# M707X.net
KiCad netlist of a schematic drawn in EAGLE
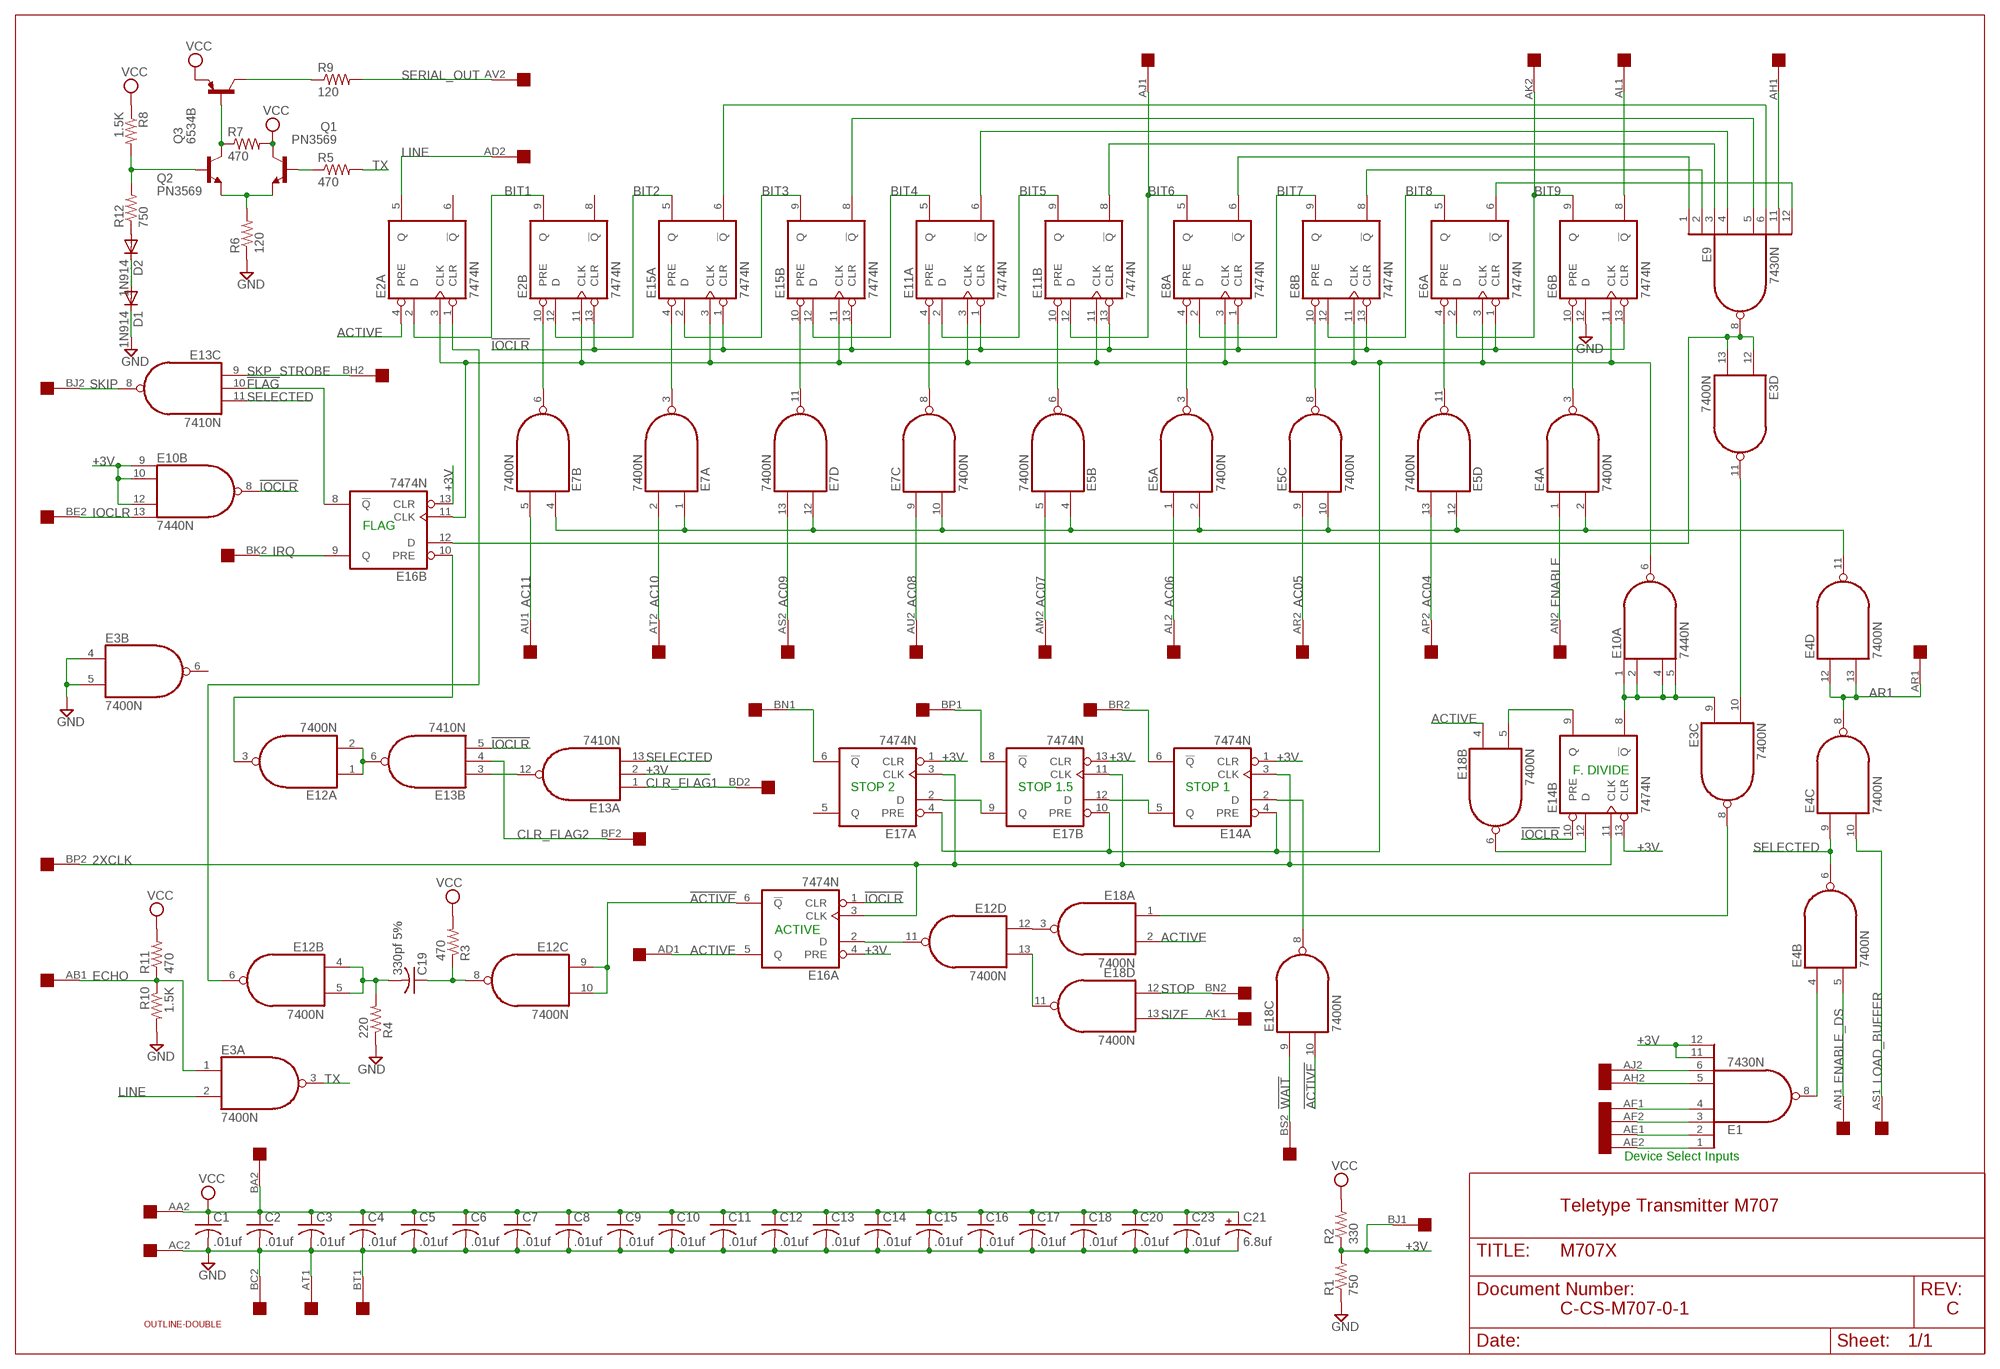
[diagram p0: schematic, sheet 1]

(export (version "E")
  (design (tool "Eeschema 10.0.6"))
  (components
    (comp (ref "C1")
      (value ".01uf")
      (footprint "eagle-import:C050-025X075")
      (libsource (lib "eagle-import") (part "C-US050-025X075"))
    )
    (comp (ref "C2")
      (value ".01uf")
      (footprint "eagle-import:C050-025X075")
      (libsource (lib "eagle-import") (part "C-US050-025X075"))
    )
    (comp (ref "C3")
      (value ".01uf")
      (footprint "eagle-import:C050-025X075")
      (libsource (lib "eagle-import") (part "C-US050-025X075"))
    )
    (comp (ref "C4")
      (value ".01uf")
      (footprint "eagle-import:C050-025X075")
      (libsource (lib "eagle-import") (part "C-US050-025X075"))
    )
    (comp (ref "C5")
      (value ".01uf")
      (footprint "eagle-import:C050-025X075")
      (libsource (lib "eagle-import") (part "C-US050-025X075"))
    )
    (comp (ref "C6")
      (value ".01uf")
      (footprint "eagle-import:C050-025X075")
      (libsource (lib "eagle-import") (part "C-US050-025X075"))
    )
    (comp (ref "C7")
      (value ".01uf")
      (footprint "eagle-import:C050-025X075")
      (libsource (lib "eagle-import") (part "C-US050-025X075"))
    )
    (comp (ref "C8")
      (value ".01uf")
      (footprint "eagle-import:C050-025X075")
      (libsource (lib "eagle-import") (part "C-US050-025X075"))
    )
    (comp (ref "C9")
      (value ".01uf")
      (footprint "eagle-import:C050-025X075")
      (libsource (lib "eagle-import") (part "C-US050-025X075"))
    )
    (comp (ref "C10")
      (value ".01uf")
      (footprint "eagle-import:C050-025X075")
      (libsource (lib "eagle-import") (part "C-US050-025X075"))
    )
    (comp (ref "C11")
      (value ".01uf")
      (footprint "eagle-import:C050-025X075")
      (libsource (lib "eagle-import") (part "C-US050-025X075"))
    )
    (comp (ref "C12")
      (value ".01uf")
      (footprint "eagle-import:C050-025X075")
      (libsource (lib "eagle-import") (part "C-US050-025X075"))
    )
    (comp (ref "C13")
      (value ".01uf")
      (footprint "eagle-import:C050-025X075")
      (libsource (lib "eagle-import") (part "C-US050-025X075"))
    )
    (comp (ref "C14")
      (value ".01uf")
      (footprint "eagle-import:C050-025X075")
      (libsource (lib "eagle-import") (part "C-US050-025X075"))
    )
    (comp (ref "C15")
      (value ".01uf")
      (footprint "eagle-import:C050-025X075")
      (libsource (lib "eagle-import") (part "C-US050-025X075"))
    )
    (comp (ref "C16")
      (value ".01uf")
      (footprint "eagle-import:C050-025X075")
      (libsource (lib "eagle-import") (part "C-US050-025X075"))
    )
    (comp (ref "C17")
      (value ".01uf")
      (footprint "eagle-import:C050-025X075")
      (libsource (lib "eagle-import") (part "C-US050-025X075"))
    )
    (comp (ref "C18")
      (value ".01uf")
      (footprint "eagle-import:C050-025X075")
      (libsource (lib "eagle-import") (part "C-US050-025X075"))
    )
    (comp (ref "C19")
      (value "330pf 5%")
      (footprint "eagle-import:C075-032X103")
      (libsource (lib "eagle-import") (part "C-US075-032X103"))
    )
    (comp (ref "C20")
      (value ".01uf")
      (footprint "eagle-import:C050-025X075")
      (libsource (lib "eagle-import") (part "C-US050-025X075"))
    )
    (comp (ref "C21")
      (value "6.8uf")
      (footprint "eagle-import:E15-5")
      (libsource (lib "eagle-import") (part "CPOL-USE15-5AXIAL"))
    )
    (comp (ref "C23")
      (value ".01uf")
      (footprint "eagle-import:C050-025X075")
      (libsource (lib "eagle-import") (part "C-US050-025X075"))
    )
    (comp (ref "D1")
      (value "1N914")
      (footprint "eagle-import:DO35-10")
      (libsource (lib "eagle-import") (part "1N4148DO35-10"))
    )
    (comp (ref "D2")
      (value "1N914")
      (footprint "eagle-import:DO35-10")
      (libsource (lib "eagle-import") (part "1N4148DO35-10"))
    )
    (comp (ref "E1")
      (value "7430N")
      (footprint "eagle-import:DIL14")
      (libsource (lib "eagle-import") (part "7430N"))
    )
    (comp (ref "E2")
      (value "7474N")
      (footprint "eagle-import:DIL14")
      (libsource (lib "eagle-import") (part "7474NS"))
    )
    (comp (ref "E3")
      (value "7400N")
      (footprint "eagle-import:DIL14")
      (libsource (lib "eagle-import") (part "7400N"))
    )
    (comp (ref "E4")
      (value "7400N")
      (footprint "eagle-import:DIL14")
      (libsource (lib "eagle-import") (part "7400N"))
    )
    (comp (ref "E5")
      (value "7400N")
      (footprint "eagle-import:DIL14")
      (libsource (lib "eagle-import") (part "7400N"))
    )
    (comp (ref "E6")
      (value "7474N")
      (footprint "eagle-import:DIL14")
      (libsource (lib "eagle-import") (part "7474NS"))
    )
    (comp (ref "E7")
      (value "7400N")
      (footprint "eagle-import:DIL14")
      (libsource (lib "eagle-import") (part "7400N"))
    )
    (comp (ref "E8")
      (value "7474N")
      (footprint "eagle-import:DIL14")
      (libsource (lib "eagle-import") (part "7474NS"))
    )
    (comp (ref "E9")
      (value "7430N")
      (footprint "eagle-import:DIL14")
      (libsource (lib "eagle-import") (part "7430N"))
    )
    (comp (ref "E10")
      (value "7440N")
      (footprint "eagle-import:DIL14")
      (libsource (lib "eagle-import") (part "7420NS"))
    )
    (comp (ref "E11")
      (value "7474N")
      (footprint "eagle-import:DIL14")
      (libsource (lib "eagle-import") (part "7474NS"))
    )
    (comp (ref "E12")
      (value "7400N")
      (footprint "eagle-import:DIL14")
      (libsource (lib "eagle-import") (part "7400N"))
    )
    (comp (ref "E13")
      (value "7410N")
      (footprint "eagle-import:DIL14")
      (libsource (lib "eagle-import") (part "7410N"))
    )
    (comp (ref "E14")
      (value "7474N")
      (footprint "eagle-import:DIL14")
      (libsource (lib "eagle-import") (part "7474NS"))
    )
    (comp (ref "E15")
      (value "7474N")
      (footprint "eagle-import:DIL14")
      (libsource (lib "eagle-import") (part "7474NS"))
    )
    (comp (ref "E16")
      (value "7474N")
      (footprint "eagle-import:DIL14")
      (libsource (lib "eagle-import") (part "7474NS"))
    )
    (comp (ref "E17")
      (value "7474N")
      (footprint "eagle-import:DIL14")
      (libsource (lib "eagle-import") (part "7474NS"))
    )
    (comp (ref "E18")
      (value "7400N")
      (footprint "eagle-import:DIL14")
      (libsource (lib "eagle-import") (part "7400N"))
    )
    (comp (ref "Q1")
      (value "PN3569")
      (footprint "eagle-import:TO39")
      (libsource (lib "eagle-import") (part "-NPN-TO39-EBC2N3440"))
    )
    (comp (ref "Q2")
      (value "PN3569")
      (footprint "eagle-import:TO39")
      (libsource (lib "eagle-import") (part "-NPN-TO39-EBC2N3440"))
    )
    (comp (ref "Q3")
      (value "6534B")
      (footprint "eagle-import:TO39")
      (libsource (lib "eagle-import") (part "-PNP-TO39-EBC2N3637"))
    )
    (comp (ref "R1")
      (value "750")
      (footprint "eagle-import:0207_10")
      (libsource (lib "eagle-import") (part "R-US_0207/10"))
    )
    (comp (ref "R2")
      (value "330")
      (footprint "eagle-import:0207_10")
      (libsource (lib "eagle-import") (part "R-US_0207/10"))
    )
    (comp (ref "R3")
      (value "470")
      (footprint "eagle-import:0207_10")
      (libsource (lib "eagle-import") (part "R-US_0207/10"))
    )
    (comp (ref "R4")
      (value "220")
      (footprint "eagle-import:0207_10")
      (libsource (lib "eagle-import") (part "R-US_0207/10"))
    )
    (comp (ref "R5")
      (value "470")
      (footprint "eagle-import:0207_10")
      (libsource (lib "eagle-import") (part "R-US_0207/10"))
    )
    (comp (ref "R6")
      (value "120")
      (footprint "eagle-import:0207_10")
      (libsource (lib "eagle-import") (part "R-US_0207/10"))
    )
    (comp (ref "R7")
      (value "470")
      (footprint "eagle-import:0207_10")
      (libsource (lib "eagle-import") (part "R-US_0207/10"))
    )
    (comp (ref "R8")
      (value "1.5K")
      (footprint "eagle-import:0207_10")
      (libsource (lib "eagle-import") (part "R-US_0207/10"))
    )
    (comp (ref "R9")
      (value "120")
      (footprint "eagle-import:0207_10")
      (libsource (lib "eagle-import") (part "R-US_0207/10"))
    )
    (comp (ref "R10")
      (value "1.5K")
      (footprint "eagle-import:0207_10")
      (libsource (lib "eagle-import") (part "R-US_0207/10"))
    )
    (comp (ref "R11")
      (value "470")
      (footprint "eagle-import:0207_10")
      (libsource (lib "eagle-import") (part "R-US_0207/10"))
    )
    (comp (ref "R12")
      (value "750")
      (footprint "eagle-import:0207_10")
      (libsource (lib "eagle-import") (part "R-US_0207/10"))
    )
    (comp (ref "U$1")
      (value "OUTLINE-DOUBLE")
      (footprint "eagle-import:DOUBLE")
      (libsource (lib "eagle-import") (part "OUTLINE-DOUBLE"))
    )
    (comp (ref "U$2")
      (value "DOUBLE")
      (footprint "eagle-import:EDGE-CON4")
      (libsource (lib "eagle-import") (part "DOUBLE"))
    )
  )
  (nets
    (net (code "1") (name "/+3V") (class "Default")
      (node (ref "E1") (pin "11") (pinfunction "I6_11") (pintype "input"))
      (node (ref "E1") (pin "12") (pinfunction "I7_12") (pintype "input"))
      (node (ref "E10") (pin "10") (pinfunction "I1_10") (pintype "input"))
      (node (ref "E10") (pin "12") (pinfunction "I2_12") (pintype "input"))
      (node (ref "E10") (pin "9") (pinfunction "I0_9") (pintype "input"))
      (node (ref "E13") (pin "2") (pinfunction "I1_2") (pintype "input"))
      (node (ref "E14") (pin "1") (pinfunction "CLR_1") (pintype "input"))
      (node (ref "E14") (pin "13") (pinfunction "CLR_13") (pintype "input"))
      (node (ref "E16") (pin "13") (pinfunction "CLR_13") (pintype "input"))
      (node (ref "E16") (pin "4") (pinfunction "PRE_4") (pintype "input"))
      (node (ref "E17") (pin "1") (pinfunction "CLR_1") (pintype "input"))
      (node (ref "E17") (pin "13") (pinfunction "CLR_13") (pintype "input"))
      (node (ref "R1") (pin "2") (pinfunction "2_2") (pintype "passive"))
      (node (ref "R2") (pin "1") (pinfunction "1_1") (pintype "passive"))
      (node (ref "U$2") (pin "BJ1") (pinfunction "1_BJ1") (pintype "bidirectional"))
    )
    (net (code "2") (name "/2XCLK") (class "Default")
      (node (ref "E14") (pin "11") (pinfunction "CLK_11") (pintype "input"))
      (node (ref "E14") (pin "3") (pinfunction "CLK_3") (pintype "input"))
      (node (ref "E16") (pin "3") (pinfunction "CLK_3") (pintype "input"))
      (node (ref "E17") (pin "11") (pinfunction "CLK_11") (pintype "input"))
      (node (ref "E17") (pin "3") (pinfunction "CLK_3") (pintype "input"))
      (node (ref "U$2") (pin "BP2") (pinfunction "1_BP2") (pintype "bidirectional"))
    )
    (net (code "3") (name "/AC04") (class "Default")
      (node (ref "E5") (pin "13") (pinfunction "I1_13") (pintype "input"))
      (node (ref "U$2") (pin "AP2") (pinfunction "1_AP2") (pintype "bidirectional"))
    )
    (net (code "4") (name "/AC05") (class "Default")
      (node (ref "E5") (pin "9") (pinfunction "I0_9") (pintype "input"))
      (node (ref "U$2") (pin "AR2") (pinfunction "1_AR2") (pintype "bidirectional"))
    )
    (net (code "5") (name "/AC06") (class "Default")
      (node (ref "E5") (pin "1") (pinfunction "I0_1") (pintype "input"))
      (node (ref "U$2") (pin "AL2") (pinfunction "1_AL2") (pintype "bidirectional"))
    )
    (net (code "6") (name "/AC07") (class "Default")
      (node (ref "E5") (pin "5") (pinfunction "I1_5") (pintype "input"))
      (node (ref "U$2") (pin "AM2") (pinfunction "1_AM2") (pintype "bidirectional"))
    )
    (net (code "7") (name "/AC08") (class "Default")
      (node (ref "E7") (pin "9") (pinfunction "I0_9") (pintype "input"))
      (node (ref "U$2") (pin "AU2") (pinfunction "1_AU2") (pintype "bidirectional"))
    )
    (net (code "8") (name "/AC09") (class "Default")
      (node (ref "E7") (pin "13") (pinfunction "I1_13") (pintype "input"))
      (node (ref "U$2") (pin "AS2") (pinfunction "1_AS2") (pintype "bidirectional"))
    )
    (net (code "9") (name "/AC10") (class "Default")
      (node (ref "E7") (pin "2") (pinfunction "I1_2") (pintype "input"))
      (node (ref "U$2") (pin "AT2") (pinfunction "1_AT2") (pintype "bidirectional"))
    )
    (net (code "10") (name "/AC11") (class "Default")
      (node (ref "E7") (pin "5") (pinfunction "I1_5") (pintype "input"))
      (node (ref "U$2") (pin "AU1") (pinfunction "1_AU1") (pintype "bidirectional"))
    )
    (net (code "11") (name "/ACTIVE") (class "Default")
      (node (ref "E16") (pin "5") (pinfunction "Q_5") (pintype "output"))
      (node (ref "E18") (pin "2") (pinfunction "I1_2") (pintype "input"))
      (node (ref "E18") (pin "4") (pinfunction "I0_4") (pintype "input"))
      (node (ref "E2") (pin "4") (pinfunction "PRE_4") (pintype "input"))
      (node (ref "U$2") (pin "AD1") (pinfunction "1_AD1") (pintype "bidirectional"))
    )
    (net (code "12") (name "/AR1") (class "Default")
      (node (ref "E4") (pin "12") (pinfunction "I0_12") (pintype "input"))
      (node (ref "E4") (pin "13") (pinfunction "I1_13") (pintype "input"))
      (node (ref "E4") (pin "8") (pinfunction "O_8") (pintype "output"))
      (node (ref "U$2") (pin "AR1") (pinfunction "1_AR1") (pintype "bidirectional"))
    )
    (net (code "13") (name "/BIT1") (class "Default")
      (node (ref "E2") (pin "2") (pinfunction "D_2") (pintype "input"))
      (node (ref "E2") (pin "9") (pinfunction "Q_9") (pintype "output"))
    )
    (net (code "14") (name "/BIT2") (class "Default")
      (node (ref "E15") (pin "5") (pinfunction "Q_5") (pintype "output"))
      (node (ref "E2") (pin "12") (pinfunction "D_12") (pintype "input"))
    )
    (net (code "15") (name "/BIT3") (class "Default")
      (node (ref "E15") (pin "2") (pinfunction "D_2") (pintype "input"))
      (node (ref "E15") (pin "9") (pinfunction "Q_9") (pintype "output"))
    )
    (net (code "16") (name "/BIT4") (class "Default")
      (node (ref "E11") (pin "5") (pinfunction "Q_5") (pintype "output"))
      (node (ref "E15") (pin "12") (pinfunction "D_12") (pintype "input"))
    )
    (net (code "17") (name "/BIT5") (class "Default")
      (node (ref "E11") (pin "2") (pinfunction "D_2") (pintype "input"))
      (node (ref "E11") (pin "9") (pinfunction "Q_9") (pintype "output"))
    )
    (net (code "18") (name "/BIT6") (class "Default")
      (node (ref "E11") (pin "12") (pinfunction "D_12") (pintype "input"))
      (node (ref "E8") (pin "5") (pinfunction "Q_5") (pintype "output"))
      (node (ref "U$2") (pin "AJ1") (pinfunction "1_AJ1") (pintype "bidirectional"))
    )
    (net (code "19") (name "/BIT7") (class "Default")
      (node (ref "E8") (pin "2") (pinfunction "D_2") (pintype "input"))
      (node (ref "E8") (pin "9") (pinfunction "Q_9") (pintype "output"))
    )
    (net (code "20") (name "/BIT8") (class "Default")
      (node (ref "E6") (pin "5") (pinfunction "Q_5") (pintype "output"))
      (node (ref "E8") (pin "12") (pinfunction "D_12") (pintype "input"))
    )
    (net (code "21") (name "/BIT9") (class "Default")
      (node (ref "E6") (pin "2") (pinfunction "D_2") (pintype "input"))
      (node (ref "E6") (pin "9") (pinfunction "Q_9") (pintype "output"))
      (node (ref "U$2") (pin "AK2") (pinfunction "1_AK2") (pintype "bidirectional"))
    )
    (net (code "22") (name "/CLR_FLAG1") (class "Default")
      (node (ref "E13") (pin "1") (pinfunction "I0_1") (pintype "input"))
      (node (ref "U$2") (pin "BD2") (pinfunction "1_BD2") (pintype "bidirectional"))
    )
    (net (code "23") (name "/CLR_FLAG2") (class "Default")
      (node (ref "E13") (pin "4") (pinfunction "I1_4") (pintype "input"))
      (node (ref "U$2") (pin "BF2") (pinfunction "1_BF2") (pintype "bidirectional"))
    )
    (net (code "24") (name "/ECHO") (class "Default")
      (node (ref "E3") (pin "1") (pinfunction "I0_1") (pintype "input"))
      (node (ref "R10") (pin "1") (pinfunction "1_1") (pintype "passive"))
      (node (ref "R11") (pin "1") (pinfunction "1_1") (pintype "passive"))
      (node (ref "U$2") (pin "AB1") (pinfunction "1_AB1") (pintype "bidirectional"))
    )
    (net (code "25") (name "/ENABLE") (class "Default")
      (node (ref "E4") (pin "1") (pinfunction "I0_1") (pintype "input"))
      (node (ref "U$2") (pin "AN2") (pinfunction "1_AN2") (pintype "bidirectional"))
    )
    (net (code "26") (name "/ENABLE_DS") (class "Default")
      (node (ref "E4") (pin "5") (pinfunction "I1_5") (pintype "input"))
      (node (ref "U$2") (pin "AN1") (pinfunction "1_AN1") (pintype "bidirectional"))
    )
    (net (code "27") (name "/IOCLR") (class "Default")
      (node (ref "E10") (pin "13") (pinfunction "I3_13") (pintype "input"))
      (node (ref "U$2") (pin "BE2") (pinfunction "1_BE2") (pintype "bidirectional"))
    )
    (net (code "28") (name "/IRQ") (class "Default")
      (node (ref "E16") (pin "9") (pinfunction "Q_9") (pintype "output"))
      (node (ref "U$2") (pin "BK2") (pinfunction "1_BK2") (pintype "bidirectional"))
    )
    (net (code "29") (name "/LINE") (class "Default")
      (node (ref "E2") (pin "5") (pinfunction "Q_5") (pintype "output"))
      (node (ref "E3") (pin "2") (pinfunction "I1_2") (pintype "input"))
      (node (ref "U$2") (pin "AD2") (pinfunction "1_AD2") (pintype "bidirectional"))
    )
    (net (code "30") (name "/LOAD_BUFFER") (class "Default")
      (node (ref "E4") (pin "10") (pinfunction "I1_10") (pintype "input"))
      (node (ref "U$2") (pin "AS1") (pinfunction "1_AS1") (pintype "bidirectional"))
    )
    (net (code "31") (name "/SELECTED") (class "Default")
      (node (ref "E13") (pin "11") (pinfunction "I2_11") (pintype "input"))
      (node (ref "E13") (pin "13") (pinfunction "I2_13") (pintype "input"))
      (node (ref "E4") (pin "6") (pinfunction "O_6") (pintype "output"))
      (node (ref "E4") (pin "9") (pinfunction "I0_9") (pintype "input"))
    )
    (net (code "32") (name "/SERIAL_OUT") (class "Default")
      (node (ref "R9") (pin "2") (pinfunction "2_2") (pintype "passive"))
      (node (ref "U$2") (pin "AV2") (pinfunction "1_AV2") (pintype "bidirectional"))
    )
    (net (code "33") (name "/SIZE") (class "Default")
      (node (ref "E18") (pin "13") (pinfunction "I1_13") (pintype "input"))
      (node (ref "U$2") (pin "AK1") (pinfunction "1_AK1") (pintype "bidirectional"))
    )
    (net (code "34") (name "/SKIP") (class "Default")
      (node (ref "E13") (pin "8") (pinfunction "O_8") (pintype "output"))
      (node (ref "U$2") (pin "BJ2") (pinfunction "1_BJ2") (pintype "bidirectional"))
    )
    (net (code "35") (name "/SKP_STROBE") (class "Default")
      (node (ref "E13") (pin "9") (pinfunction "I0_9") (pintype "input"))
      (node (ref "U$2") (pin "BH2") (pinfunction "1_BH2") (pintype "bidirectional"))
    )
    (net (code "36") (name "/STOP") (class "Default")
      (node (ref "E18") (pin "12") (pinfunction "I0_12") (pintype "input"))
      (node (ref "U$2") (pin "BN2") (pinfunction "1_BN2") (pintype "bidirectional"))
    )
    (net (code "37") (name "/TX") (class "Default")
      (node (ref "E3") (pin "3") (pinfunction "O_3") (pintype "output"))
      (node (ref "R5") (pin "2") (pinfunction "2_2") (pintype "passive"))
    )
    (net (code "38") (name "/~{ACTIVE}") (class "Default")
      (node (ref "E12") (pin "10") (pinfunction "I1_10") (pintype "input"))
      (node (ref "E12") (pin "9") (pinfunction "I0_9") (pintype "input"))
      (node (ref "E16") (pin "6") (pinfunction "~{Q}_6") (pintype "output"))
      (node (ref "E18") (pin "10") (pinfunction "I1_10") (pintype "input"))
    )
    (net (code "39") (name "/~{FLAG}") (class "Default")
      (node (ref "E13") (pin "10") (pinfunction "I1_10") (pintype "input"))
      (node (ref "E16") (pin "8") (pinfunction "~{Q}_8") (pintype "output"))
    )
    (net (code "40") (name "/~{IOCLR}") (class "Default")
      (node (ref "E10") (pin "8") (pinfunction "O_8") (pintype "output"))
      (node (ref "E11") (pin "1") (pinfunction "CLR_1") (pintype "input"))
      (node (ref "E11") (pin "13") (pinfunction "CLR_13") (pintype "input"))
      (node (ref "E13") (pin "5") (pinfunction "I2_5") (pintype "input"))
      (node (ref "E14") (pin "10") (pinfunction "PRE_10") (pintype "input"))
      (node (ref "E15") (pin "1") (pinfunction "CLR_1") (pintype "input"))
      (node (ref "E15") (pin "13") (pinfunction "CLR_13") (pintype "input"))
      (node (ref "E16") (pin "1") (pinfunction "CLR_1") (pintype "input"))
      (node (ref "E2") (pin "13") (pinfunction "CLR_13") (pintype "input"))
      (node (ref "E6") (pin "1") (pinfunction "CLR_1") (pintype "input"))
      (node (ref "E6") (pin "13") (pinfunction "CLR_13") (pintype "input"))
      (node (ref "E8") (pin "1") (pinfunction "CLR_1") (pintype "input"))
      (node (ref "E8") (pin "13") (pinfunction "CLR_13") (pintype "input"))
    )
    (net (code "41") (name "/~{WAIT}") (class "Default")
      (node (ref "E18") (pin "9") (pinfunction "I0_9") (pintype "input"))
      (node (ref "U$2") (pin "BS2") (pinfunction "1_BS2") (pintype "bidirectional"))
    )
    (net (code "42") (name "GND") (class "Default")
      (node (ref "C1") (pin "2") (pinfunction "2_2") (pintype "passive"))
      (node (ref "C10") (pin "2") (pinfunction "2_2") (pintype "passive"))
      (node (ref "C11") (pin "2") (pinfunction "2_2") (pintype "passive"))
      (node (ref "C12") (pin "2") (pinfunction "2_2") (pintype "passive"))
      (node (ref "C13") (pin "2") (pinfunction "2_2") (pintype "passive"))
      (node (ref "C14") (pin "2") (pinfunction "2_2") (pintype "passive"))
      (node (ref "C15") (pin "2") (pinfunction "2_2") (pintype "passive"))
      (node (ref "C16") (pin "2") (pinfunction "2_2") (pintype "passive"))
      (node (ref "C17") (pin "2") (pinfunction "2_2") (pintype "passive"))
      (node (ref "C18") (pin "2") (pinfunction "2_2") (pintype "passive"))
      (node (ref "C2") (pin "2") (pinfunction "2_2") (pintype "passive"))
      (node (ref "C20") (pin "2") (pinfunction "2_2") (pintype "passive"))
      (node (ref "C21") (pin "-") (pinfunction "-_-") (pintype "passive"))
      (node (ref "C23") (pin "2") (pinfunction "2_2") (pintype "passive"))
      (node (ref "C3") (pin "2") (pinfunction "2_2") (pintype "passive"))
      (node (ref "C4") (pin "2") (pinfunction "2_2") (pintype "passive"))
      (node (ref "C5") (pin "2") (pinfunction "2_2") (pintype "passive"))
      (node (ref "C6") (pin "2") (pinfunction "2_2") (pintype "passive"))
      (node (ref "C7") (pin "2") (pinfunction "2_2") (pintype "passive"))
      (node (ref "C8") (pin "2") (pinfunction "2_2") (pintype "passive"))
      (node (ref "C9") (pin "2") (pinfunction "2_2") (pintype "passive"))
      (node (ref "D1") (pin "C") (pinfunction "C_C") (pintype "passive"))
      (node (ref "E3") (pin "4") (pinfunction "I0_4") (pintype "input"))
      (node (ref "E3") (pin "5") (pinfunction "I1_5") (pintype "input"))
      (node (ref "E6") (pin "12") (pinfunction "D_12") (pintype "input"))
      (node (ref "R1") (pin "1") (pinfunction "1_1") (pintype "passive"))
      (node (ref "R10") (pin "2") (pinfunction "2_2") (pintype "passive"))
      (node (ref "R4") (pin "1") (pinfunction "1_1") (pintype "passive"))
      (node (ref "R6") (pin "1") (pinfunction "1_1") (pintype "passive"))
      (node (ref "U$2") (pin "AC2") (pinfunction "1_AC2") (pintype "bidirectional"))
      (node (ref "U$2") (pin "AT1") (pinfunction "1_AT1") (pintype "bidirectional"))
      (node (ref "U$2") (pin "BC2") (pinfunction "1_BC2") (pintype "bidirectional"))
      (node (ref "U$2") (pin "BT1") (pinfunction "1_BT1") (pintype "bidirectional"))
    )
    (net (code "43") (name "Net-(D1-PadA)") (class "Default")
      (node (ref "D1") (pin "A") (pinfunction "A_A") (pintype "passive"))
      (node (ref "D2") (pin "C") (pinfunction "C_C") (pintype "passive"))
    )
    (net (code "44") (name "Net-(D2-PadA)") (class "Default")
      (node (ref "D2") (pin "A") (pinfunction "A_A") (pintype "passive"))
      (node (ref "R12") (pin "1") (pinfunction "1_1") (pintype "passive"))
    )
    (net (code "45") (name "Net-(E1A-I0)") (class "Default")
      (node (ref "E1") (pin "1") (pinfunction "I0_1") (pintype "input"))
      (node (ref "U$2") (pin "AE2") (pinfunction "1_AE2") (pintype "bidirectional"))
    )
    (net (code "46") (name "Net-(E1A-I1)") (class "Default")
      (node (ref "E1") (pin "2") (pinfunction "I1_2") (pintype "input"))
      (node (ref "U$2") (pin "AE1") (pinfunction "1_AE1") (pintype "bidirectional"))
    )
    (net (code "47") (name "Net-(E1A-I2)") (class "Default")
      (node (ref "E1") (pin "3") (pinfunction "I2_3") (pintype "input"))
      (node (ref "U$2") (pin "AF2") (pinfunction "1_AF2") (pintype "bidirectional"))
    )
    (net (code "48") (name "Net-(E1A-I3)") (class "Default")
      (node (ref "E1") (pin "4") (pinfunction "I3_4") (pintype "input"))
      (node (ref "U$2") (pin "AF1") (pinfunction "1_AF1") (pintype "bidirectional"))
    )
    (net (code "49") (name "Net-(E1A-I4)") (class "Default")
      (node (ref "E1") (pin "5") (pinfunction "I4_5") (pintype "input"))
      (node (ref "U$2") (pin "AH2") (pinfunction "1_AH2") (pintype "bidirectional"))
    )
    (net (code "50") (name "Net-(E1A-I5)") (class "Default")
      (node (ref "E1") (pin "6") (pinfunction "I5_6") (pintype "input"))
      (node (ref "U$2") (pin "AJ2") (pinfunction "1_AJ2") (pintype "bidirectional"))
    )
    (net (code "51") (name "Net-(E1A-O)") (class "Default")
      (node (ref "E1") (pin "8") (pinfunction "O_8") (pintype "output"))
      (node (ref "E4") (pin "4") (pinfunction "I0_4") (pintype "input"))
    )
    (net (code "52") (name "Net-(E2B-PRE)") (class "Default")
      (node (ref "E2") (pin "10") (pinfunction "PRE_10") (pintype "input"))
      (node (ref "E7") (pin "6") (pinfunction "O_6") (pintype "output"))
    )
    (net (code "53") (name "Net-(E3C-I1)") (class "Default")
      (node (ref "E3") (pin "10") (pinfunction "I1_10") (pintype "input"))
      (node (ref "E3") (pin "11") (pinfunction "O_11") (pintype "output"))
    )
    (net (code "54") (name "Net-(E4A-I1)") (class "Default")
      (node (ref "E4") (pin "11") (pinfunction "O_11") (pintype "output"))
      (node (ref "E4") (pin "2") (pinfunction "I1_2") (pintype "input"))
      (node (ref "E5") (pin "10") (pinfunction "I1_10") (pintype "input"))
      (node (ref "E5") (pin "12") (pinfunction "I0_12") (pintype "input"))
      (node (ref "E5") (pin "2") (pinfunction "I1_2") (pintype "input"))
      (node (ref "E5") (pin "4") (pinfunction "I0_4") (pintype "input"))
      (node (ref "E7") (pin "1") (pinfunction "I0_1") (pintype "input"))
      (node (ref "E7") (pin "10") (pinfunction "I1_10") (pintype "input"))
      (node (ref "E7") (pin "12") (pinfunction "I0_12") (pintype "input"))
      (node (ref "E7") (pin "4") (pinfunction "I0_4") (pintype "input"))
    )
    (net (code "55") (name "Net-(E4A-O)") (class "Default")
      (node (ref "E4") (pin "3") (pinfunction "O_3") (pintype "output"))
      (node (ref "E6") (pin "10") (pinfunction "PRE_10") (pintype "input"))
    )
    (net (code "56") (name "Net-(E5A-O)") (class "Default")
      (node (ref "E5") (pin "3") (pinfunction "O_3") (pintype "output"))
      (node (ref "E8") (pin "4") (pinfunction "PRE_4") (pintype "input"))
    )
    (net (code "57") (name "Net-(E5C-O)") (class "Default")
      (node (ref "E5") (pin "8") (pinfunction "O_8") (pintype "output"))
      (node (ref "E8") (pin "10") (pinfunction "PRE_10") (pintype "input"))
    )
    (net (code "58") (name "Net-(E5D-O)") (class "Default")
      (node (ref "E5") (pin "11") (pinfunction "O_11") (pintype "output"))
      (node (ref "E6") (pin "4") (pinfunction "PRE_4") (pintype "input"))
    )
    (net (code "59") (name "Net-(E6A-~{Q})") (class "Default")
      (node (ref "E6") (pin "6") (pinfunction "~{Q}_6") (pintype "output"))
      (node (ref "E9") (pin "12") (pinfunction "I7_12") (pintype "input"))
    )
    (net (code "60") (name "Net-(E6B-~{Q})") (class "Default")
      (node (ref "E6") (pin "8") (pinfunction "~{Q}_8") (pintype "output"))
      (node (ref "U$2") (pin "AL1") (pinfunction "1_AL1") (pintype "bidirectional"))
    )
    (net (code "61") (name "Net-(E8A-~{Q})") (class "Default")
      (node (ref "E8") (pin "6") (pinfunction "~{Q}_6") (pintype "output"))
      (node (ref "E9") (pin "1") (pinfunction "I0_1") (pintype "input"))
    )
    (net (code "62") (name "Net-(E8B-~{Q})") (class "Default")
      (node (ref "E8") (pin "8") (pinfunction "~{Q}_8") (pintype "output"))
      (node (ref "E9") (pin "2") (pinfunction "I1_2") (pintype "input"))
    )
    (net (code "63") (name "Net-(E9A-I6)") (class "Default")
      (node (ref "E9") (pin "11") (pinfunction "I6_11") (pintype "input"))
      (node (ref "U$2") (pin "AH1") (pinfunction "1_AH1") (pintype "bidirectional"))
    )
    (net (code "64") (name "Net-(E10A-I0)") (class "Default")
      (node (ref "E10") (pin "1") (pinfunction "I0_1") (pintype "input"))
      (node (ref "E10") (pin "2") (pinfunction "I1_2") (pintype "input"))
      (node (ref "E10") (pin "4") (pinfunction "I2_4") (pintype "input"))
      (node (ref "E10") (pin "5") (pinfunction "I3_5") (pintype "input"))
      (node (ref "E14") (pin "8") (pinfunction "~{Q}_8") (pintype "output"))
      (node (ref "E3") (pin "9") (pinfunction "I0_9") (pintype "input"))
    )
    (net (code "65") (name "Net-(E10A-O)") (class "Default")
      (node (ref "E10") (pin "6") (pinfunction "O_6") (pintype "output"))
      (node (ref "E11") (pin "11") (pinfunction "CLK_11") (pintype "input"))
      (node (ref "E11") (pin "3") (pinfunction "CLK_3") (pintype "input"))
      (node (ref "E14") (pin "4") (pinfunction "PRE_4") (pintype "input"))
      (node (ref "E15") (pin "11") (pinfunction "CLK_11") (pintype "input"))
      (node (ref "E15") (pin "3") (pinfunction "CLK_3") (pintype "input"))
      (node (ref "E16") (pin "11") (pinfunction "CLK_11") (pintype "input"))
      (node (ref "E17") (pin "10") (pinfunction "PRE_10") (pintype "input"))
      (node (ref "E17") (pin "4") (pinfunction "PRE_4") (pintype "input"))
      (node (ref "E2") (pin "11") (pinfunction "CLK_11") (pintype "input"))
      (node (ref "E2") (pin "3") (pinfunction "CLK_3") (pintype "input"))
      (node (ref "E6") (pin "11") (pinfunction "CLK_11") (pintype "input"))
      (node (ref "E6") (pin "3") (pinfunction "CLK_3") (pintype "input"))
      (node (ref "E8") (pin "11") (pinfunction "CLK_11") (pintype "input"))
      (node (ref "E8") (pin "3") (pinfunction "CLK_3") (pintype "input"))
    )
    (net (code "66") (name "Net-(E11A-PRE)") (class "Default")
      (node (ref "E11") (pin "4") (pinfunction "PRE_4") (pintype "input"))
      (node (ref "E7") (pin "8") (pinfunction "O_8") (pintype "output"))
    )
    (net (code "67") (name "Net-(E11A-~{Q})") (class "Default")
      (node (ref "E11") (pin "6") (pinfunction "~{Q}_6") (pintype "output"))
      (node (ref "E9") (pin "4") (pinfunction "I3_4") (pintype "input"))
    )
    (net (code "68") (name "Net-(E11B-PRE)") (class "Default")
      (node (ref "E11") (pin "10") (pinfunction "PRE_10") (pintype "input"))
      (node (ref "E5") (pin "6") (pinfunction "O_6") (pintype "output"))
    )
    (net (code "69") (name "Net-(E11B-~{Q})") (class "Default")
      (node (ref "E11") (pin "8") (pinfunction "~{Q}_8") (pintype "output"))
      (node (ref "E9") (pin "3") (pinfunction "I2_3") (pintype "input"))
    )
    (net (code "70") (name "Net-(E12A-I0)") (class "Default")
      (node (ref "E12") (pin "1") (pinfunction "I0_1") (pintype "input"))
      (node (ref "E12") (pin "2") (pinfunction "I1_2") (pintype "input"))
      (node (ref "E13") (pin "6") (pinfunction "O_6") (pintype "output"))
    )
    (net (code "71") (name "Net-(E12A-O)") (class "Default")
      (node (ref "E12") (pin "3") (pinfunction "O_3") (pintype "output"))
      (node (ref "E16") (pin "10") (pinfunction "PRE_10") (pintype "input"))
    )
    (net (code "72") (name "Net-(E12B-I0)") (class "Default")
      (node (ref "C19") (pin "2") (pinfunction "2_2") (pintype "passive"))
      (node (ref "E12") (pin "4") (pinfunction "I0_4") (pintype "input"))
      (node (ref "E12") (pin "5") (pinfunction "I1_5") (pintype "input"))
      (node (ref "R4") (pin "2") (pinfunction "2_2") (pintype "passive"))
    )
    (net (code "73") (name "Net-(E12B-O)") (class "Default")
      (node (ref "E12") (pin "6") (pinfunction "O_6") (pintype "output"))
      (node (ref "E2") (pin "1") (pinfunction "CLR_1") (pintype "input"))
    )
    (net (code "74") (name "Net-(E12C-O)") (class "Default")
      (node (ref "C19") (pin "1") (pinfunction "1_1") (pintype "passive"))
      (node (ref "E12") (pin "8") (pinfunction "O_8") (pintype "output"))
      (node (ref "R3") (pin "1") (pinfunction "1_1") (pintype "passive"))
    )
    (net (code "75") (name "Net-(E12D-I0)") (class "Default")
      (node (ref "E12") (pin "12") (pinfunction "I0_12") (pintype "input"))
      (node (ref "E18") (pin "3") (pinfunction "O_3") (pintype "output"))
    )
    (net (code "76") (name "Net-(E12D-I1)") (class "Default")
      (node (ref "E12") (pin "13") (pinfunction "I1_13") (pintype "input"))
      (node (ref "E18") (pin "11") (pinfunction "O_11") (pintype "output"))
    )
    (net (code "77") (name "Net-(E12D-O)") (class "Default")
      (node (ref "E12") (pin "11") (pinfunction "O_11") (pintype "output"))
      (node (ref "E16") (pin "2") (pinfunction "D_2") (pintype "input"))
    )
    (net (code "78") (name "Net-(E13A-O)") (class "Default")
      (node (ref "E13") (pin "12") (pinfunction "O_12") (pintype "output"))
      (node (ref "E13") (pin "3") (pinfunction "I0_3") (pintype "input"))
    )
    (net (code "79") (name "Net-(E14A-D)") (class "Default")
      (node (ref "E14") (pin "2") (pinfunction "D_2") (pintype "input"))
      (node (ref "E18") (pin "8") (pinfunction "O_8") (pintype "output"))
    )
    (net (code "80") (name "Net-(E14A-Q)") (class "Default")
      (node (ref "E14") (pin "5") (pinfunction "Q_5") (pintype "output"))
      (node (ref "E17") (pin "12") (pinfunction "D_12") (pintype "input"))
    )
    (net (code "81") (name "Net-(E14A-~{Q})") (class "Default")
      (node (ref "E14") (pin "6") (pinfunction "~{Q}_6") (pintype "output"))
      (node (ref "U$2") (pin "BR2") (pinfunction "1_BR2") (pintype "bidirectional"))
    )
    (net (code "82") (name "Net-(E14B-D)") (class "Default")
      (node (ref "E14") (pin "12") (pinfunction "D_12") (pintype "input"))
      (node (ref "E18") (pin "6") (pinfunction "O_6") (pintype "output"))
    )
    (net (code "83") (name "Net-(E14B-Q)") (class "Default")
      (node (ref "E14") (pin "9") (pinfunction "Q_9") (pintype "output"))
      (node (ref "E18") (pin "5") (pinfunction "I1_5") (pintype "input"))
    )
    (net (code "84") (name "Net-(E15A-PRE)") (class "Default")
      (node (ref "E15") (pin "4") (pinfunction "PRE_4") (pintype "input"))
      (node (ref "E7") (pin "3") (pinfunction "O_3") (pintype "output"))
    )
    (net (code "85") (name "Net-(E15A-~{Q})") (class "Default")
      (node (ref "E15") (pin "6") (pinfunction "~{Q}_6") (pintype "output"))
      (node (ref "E9") (pin "6") (pinfunction "I5_6") (pintype "input"))
    )
    (net (code "86") (name "Net-(E15B-PRE)") (class "Default")
      (node (ref "E15") (pin "10") (pinfunction "PRE_10") (pintype "input"))
      (node (ref "E7") (pin "11") (pinfunction "O_11") (pintype "output"))
    )
    (net (code "87") (name "Net-(E15B-~{Q})") (class "Default")
      (node (ref "E15") (pin "8") (pinfunction "~{Q}_8") (pintype "output"))
      (node (ref "E9") (pin "5") (pinfunction "I4_5") (pintype "input"))
    )
    (net (code "88") (name "Net-(E16B-D)") (class "Default")
      (node (ref "E16") (pin "12") (pinfunction "D_12") (pintype "input"))
      (node (ref "E3") (pin "12") (pinfunction "I0_12") (pintype "input"))
      (node (ref "E3") (pin "13") (pinfunction "I1_13") (pintype "input"))
      (node (ref "E9") (pin "8") (pinfunction "O_8") (pintype "output"))
    )
    (net (code "89") (name "Net-(E17A-D)") (class "Default")
      (node (ref "E17") (pin "2") (pinfunction "D_2") (pintype "input"))
      (node (ref "E17") (pin "9") (pinfunction "Q_9") (pintype "output"))
    )
    (net (code "90") (name "Net-(E17A-~{Q})") (class "Default")
      (node (ref "E17") (pin "6") (pinfunction "~{Q}_6") (pintype "output"))
      (node (ref "U$2") (pin "BN1") (pinfunction "1_BN1") (pintype "bidirectional"))
    )
    (net (code "91") (name "Net-(E17B-~{Q})") (class "Default")
      (node (ref "E17") (pin "8") (pinfunction "~{Q}_8") (pintype "output"))
      (node (ref "U$2") (pin "BP1") (pinfunction "1_BP1") (pintype "bidirectional"))
    )
    (net (code "92") (name "Net-(E18A-I0)") (class "Default")
      (node (ref "E18") (pin "1") (pinfunction "I0_1") (pintype "input"))
      (node (ref "E3") (pin "8") (pinfunction "O_8") (pintype "output"))
    )
    (net (code "93") (name "Net-(Q1-B)") (class "Default")
      (node (ref "Q1") (pin "2") (pinfunction "B_2") (pintype "passive"))
      (node (ref "R5") (pin "1") (pinfunction "1_1") (pintype "passive"))
    )
    (net (code "94") (name "Net-(Q1-E)") (class "Default")
      (node (ref "Q1") (pin "1") (pinfunction "E_1") (pintype "passive"))
      (node (ref "Q2") (pin "1") (pinfunction "E_1") (pintype "passive"))
      (node (ref "R6") (pin "2") (pinfunction "2_2") (pintype "passive"))
    )
    (net (code "95") (name "Net-(Q2-B)") (class "Default")
      (node (ref "Q2") (pin "2") (pinfunction "B_2") (pintype "passive"))
      (node (ref "R12") (pin "2") (pinfunction "2_2") (pintype "passive"))
      (node (ref "R8") (pin "2") (pinfunction "2_2") (pintype "passive"))
    )
    (net (code "96") (name "Net-(Q2-C)") (class "Default")
      (node (ref "Q2") (pin "3") (pinfunction "C_3") (pintype "passive"))
      (node (ref "Q3") (pin "2") (pinfunction "B_2") (pintype "passive"))
      (node (ref "R7") (pin "1") (pinfunction "1_1") (pintype "passive"))
    )
    (net (code "97") (name "Net-(Q3-C)") (class "Default")
      (node (ref "Q3") (pin "3") (pinfunction "C_3") (pintype "passive"))
      (node (ref "R9") (pin "1") (pinfunction "1_1") (pintype "passive"))
    )
    (net (code "98") (name "VCC") (class "Default")
      (node (ref "C1") (pin "1") (pinfunction "1_1") (pintype "passive"))
      (node (ref "C10") (pin "1") (pinfunction "1_1") (pintype "passive"))
      (node (ref "C11") (pin "1") (pinfunction "1_1") (pintype "passive"))
      (node (ref "C12") (pin "1") (pinfunction "1_1") (pintype "passive"))
      (node (ref "C13") (pin "1") (pinfunction "1_1") (pintype "passive"))
      (node (ref "C14") (pin "1") (pinfunction "1_1") (pintype "passive"))
      (node (ref "C15") (pin "1") (pinfunction "1_1") (pintype "passive"))
      (node (ref "C16") (pin "1") (pinfunction "1_1") (pintype "passive"))
      (node (ref "C17") (pin "1") (pinfunction "1_1") (pintype "passive"))
      (node (ref "C18") (pin "1") (pinfunction "1_1") (pintype "passive"))
      (node (ref "C2") (pin "1") (pinfunction "1_1") (pintype "passive"))
      (node (ref "C20") (pin "1") (pinfunction "1_1") (pintype "passive"))
      (node (ref "C21") (pin "+") (pinfunction "+_+") (pintype "passive"))
      (node (ref "C23") (pin "1") (pinfunction "1_1") (pintype "passive"))
      (node (ref "C3") (pin "1") (pinfunction "1_1") (pintype "passive"))
      (node (ref "C4") (pin "1") (pinfunction "1_1") (pintype "passive"))
      (node (ref "C5") (pin "1") (pinfunction "1_1") (pintype "passive"))
      (node (ref "C6") (pin "1") (pinfunction "1_1") (pintype "passive"))
      (node (ref "C7") (pin "1") (pinfunction "1_1") (pintype "passive"))
      (node (ref "C8") (pin "1") (pinfunction "1_1") (pintype "passive"))
      (node (ref "C9") (pin "1") (pinfunction "1_1") (pintype "passive"))
      (node (ref "Q1") (pin "3") (pinfunction "C_3") (pintype "passive"))
      (node (ref "Q3") (pin "1") (pinfunction "E_1") (pintype "passive"))
      (node (ref "R11") (pin "2") (pinfunction "2_2") (pintype "passive"))
      (node (ref "R2") (pin "2") (pinfunction "2_2") (pintype "passive"))
      (node (ref "R3") (pin "2") (pinfunction "2_2") (pintype "passive"))
      (node (ref "R7") (pin "2") (pinfunction "2_2") (pintype "passive"))
      (node (ref "R8") (pin "1") (pinfunction "1_1") (pintype "passive"))
      (node (ref "U$2") (pin "AA2") (pinfunction "1_AA2") (pintype "bidirectional"))
      (node (ref "U$2") (pin "BA2") (pinfunction "1_BA2") (pintype "bidirectional"))
    )
    (net (code "99") (name "unconnected-(E2A-~{Q}-Pad6)") (class "Default")
      (node (ref "E2") (pin "6") (pinfunction "~{Q}_6") (pintype "output"))
    )
    (net (code "100") (name "unconnected-(E2B-~{Q}-Pad8)") (class "Default")
      (node (ref "E2") (pin "8") (pinfunction "~{Q}_8") (pintype "output"))
    )
    (net (code "101") (name "unconnected-(E3B-O-Pad6)") (class "Default")
      (node (ref "E3") (pin "6") (pinfunction "O_6") (pintype "output"))
    )
    (net (code "102") (name "unconnected-(E17A-Q-Pad5)") (class "Default")
      (node (ref "E17") (pin "5") (pinfunction "Q_5") (pintype "output"))
    )
  )
)
